# mcu.net
KiCad netlist of a schematic drawn in Altium Designer
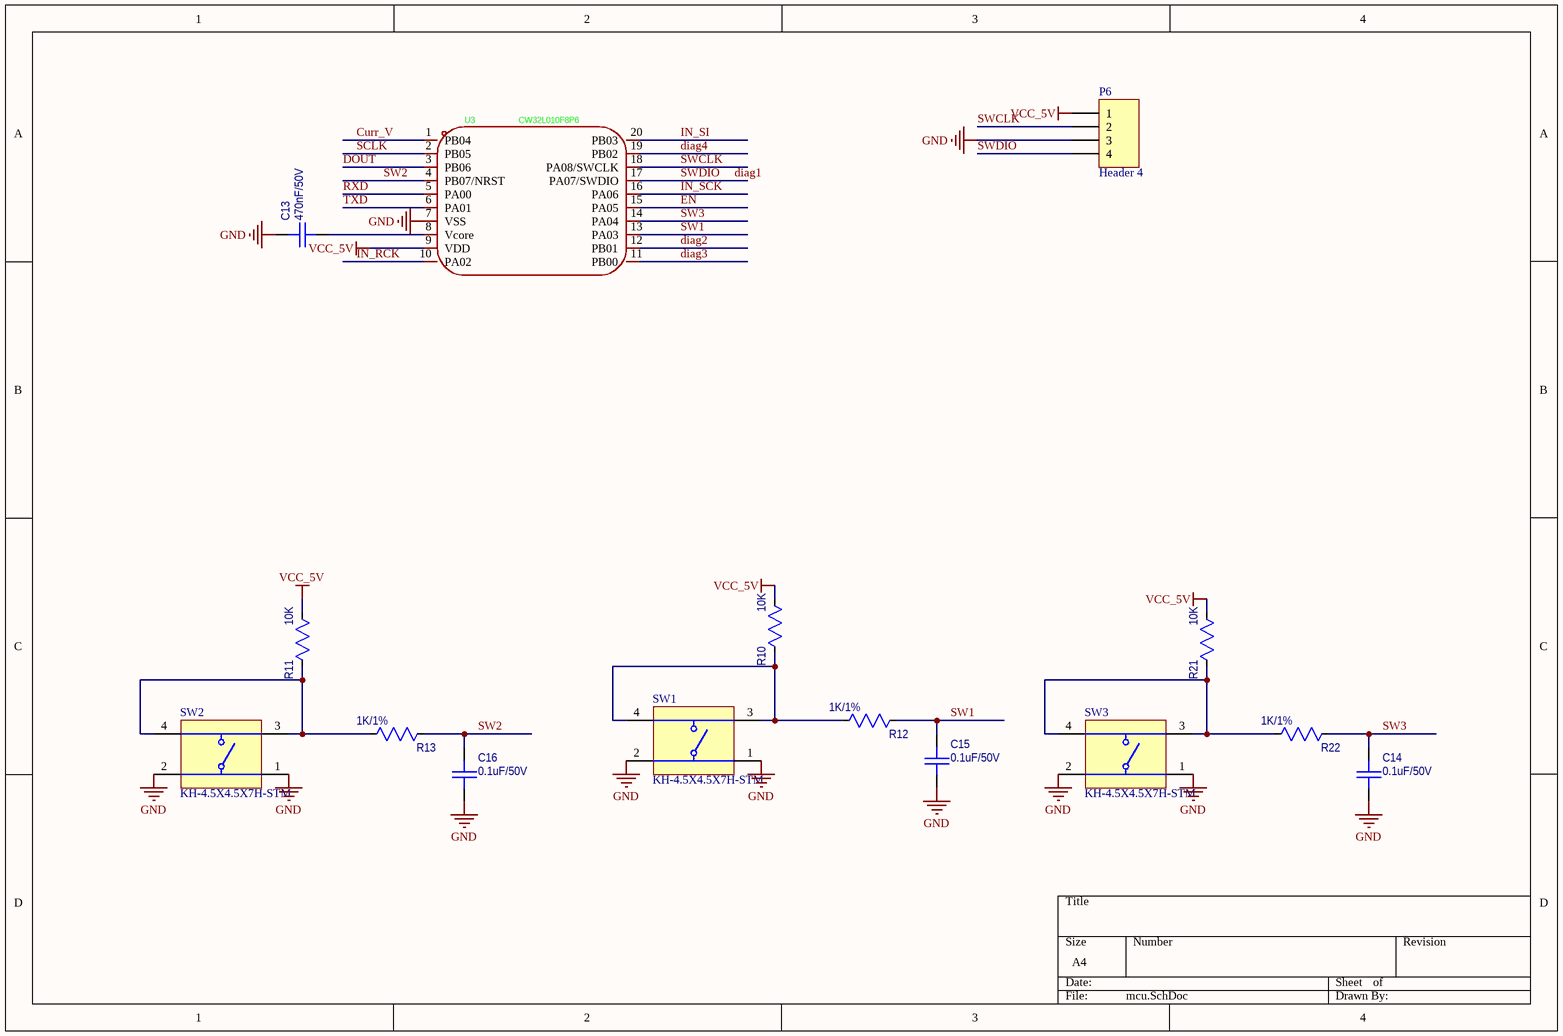
[diagram p0: mcu.SchDoc]

(export (version "E")
  (design (tool "Eeschema 10.0.6"))
  (components
    (comp (ref "C13")
      (value "470nF/50V")
      (footprint "CAPC1608X092N_0603")
      (description "Capacitor, MLCC")
      (fields (field (name "MANUFACTURER") "KEMET") (field (name "PARTNUMBER") "C0603C104M5RACTU"))
      (libsource (lib "Karl") (part "Capacitor_0603"))
    )
    (comp (ref "C14")
      (value "0.1uF/50V")
      (footprint "CAPC1608X092N_0603")
      (description "Capacitor, MLCC")
      (fields (field (name "MANUFACTURER") "KEMET") (field (name "PARTNUMBER") "C0603C104M5RACTU"))
      (libsource (lib "Karl") (part "Capacitor_0603"))
    )
    (comp (ref "C15")
      (value "0.1uF/50V")
      (footprint "CAPC1608X092N_0603")
      (description "Capacitor, MLCC")
      (fields (field (name "MANUFACTURER") "KEMET") (field (name "PARTNUMBER") "C0603C104M5RACTU"))
      (libsource (lib "Karl") (part "Capacitor_0603"))
    )
    (comp (ref "C16")
      (value "0.1uF/50V")
      (footprint "CAPC1608X092N_0603")
      (description "Capacitor, MLCC")
      (fields (field (name "MANUFACTURER") "KEMET") (field (name "PARTNUMBER") "C0603C104M5RACTU"))
      (libsource (lib "Karl") (part "Capacitor_0603"))
    )
    (comp (ref "P6")
      (value "Header 4")
      (footprint "1.27-4P")
      (fields (field (name "PUBLISHER") "Altium Limited"))
      (libsource (lib "Miscellaneous Connectors") (part "Header 4"))
    )
    (comp (ref "R10")
      (value "10K")
      (footprint "RESC1608X055N_0603")
      (description "Resistor, Standard")
      (fields (field (name "MANUFACTURER") "Yageo") (field (name "PARTNUMBER") "RC0603FR-1075KL"))
      (libsource (lib "Karl") (part "Resistor_0603"))
    )
    (comp (ref "R11")
      (value "10K")
      (footprint "RESC1608X055N_0603")
      (description "Resistor, Standard")
      (fields (field (name "MANUFACTURER") "Yageo") (field (name "PARTNUMBER") "RC0603FR-1075KL"))
      (libsource (lib "Karl") (part "Resistor_0603"))
    )
    (comp (ref "R12")
      (value "1K/1%")
      (footprint "RESC1608X055N_0603")
      (description "Resistor, Standard")
      (fields (field (name "MANUFACTURER") "Yageo") (field (name "PARTNUMBER") "RC0603FR-1075KL"))
      (libsource (lib "Karl") (part "Resistor_0603"))
    )
    (comp (ref "R13")
      (value "1K/1%")
      (footprint "RESC1608X055N_0603")
      (description "Resistor, Standard")
      (fields (field (name "MANUFACTURER") "Yageo") (field (name "PARTNUMBER") "RC0603FR-1075KL"))
      (libsource (lib "Karl") (part "Resistor_0603"))
    )
    (comp (ref "R21")
      (value "10K")
      (footprint "RESC1608X055N_0603")
      (description "Resistor, Standard")
      (fields (field (name "MANUFACTURER") "Yageo") (field (name "PARTNUMBER") "RC0603FR-1075KL"))
      (libsource (lib "Karl") (part "Resistor_0603"))
    )
    (comp (ref "R22")
      (value "1K/1%")
      (footprint "RESC1608X055N_0603")
      (description "Resistor, Standard")
      (fields (field (name "MANUFACTURER") "Yageo") (field (name "PARTNUMBER") "RC0603FR-1075KL"))
      (libsource (lib "Karl") (part "Resistor_0603"))
    )
    (comp (ref "SW1")
      (value "KH-4.5X4.5X7H-STM")
      (footprint "SW-SMD_4P-L4.5-W4.5-P3.00-LS6.8:SW-SMD_4P-L4.5-W4.5-P3.00-LS6.8")
      (description "Tactile Switch, 6 × 6 mm, Height 5.0mm, 4-Pin THD")
      (fields (field (name "PARTNUMBER") "J1L0503110"))
      (libsource (lib "Bogen") (part "J1L0503110"))
    )
    (comp (ref "SW2")
      (value "KH-4.5X4.5X7H-STM")
      (footprint "SW-SMD_4P-L4.5-W4.5-P3.00-LS6.8:SW-SMD_4P-L4.5-W4.5-P3.00-LS6.8")
      (description "Tactile Switch, 6 × 6 mm, Height 5.0mm, 4-Pin THD")
      (fields (field (name "PARTNUMBER") "J1L0503110"))
      (libsource (lib "Bogen") (part "J1L0503110"))
    )
    (comp (ref "SW3")
      (value "KH-4.5X4.5X7H-STM")
      (footprint "SW-SMD_4P-L4.5-W4.5-P3.00-LS6.8:SW-SMD_4P-L4.5-W4.5-P3.00-LS6.8")
      (description "Tactile Switch, 6 × 6 mm, Height 5.0mm, 4-Pin THD")
      (fields (field (name "PARTNUMBER") "J1L0503110"))
      (libsource (lib "Bogen") (part "J1L0503110"))
    )
    (comp (ref "U3")
      (value "CW32L010F8P6")
      (footprint "TSSOP-20_L6.5-W4.4-P0.65-LS6.4-BL:TSSOP-20_L6.5-W4.4-P0.65-LS6.4-BL")
      (fields (field (name "MANUFACTURER") "CW(芯源)"))
      (libsource (lib "altium-import") (part "root_0_CW32L010F8P6_"))
    )
  )
  (nets
    (net (code "1") (name "/Curr_V") (class "Default")
      (node (ref "U3") (pin "1") (pinfunction "PB04_1") (pintype "passive"))
    )
    (net (code "2") (name "/DOUT") (class "Default")
      (node (ref "U3") (pin "3") (pinfunction "PB06_3") (pintype "passive"))
    )
    (net (code "3") (name "/EN") (class "Default")
      (node (ref "U3") (pin "15") (pinfunction "PA05_15") (pintype "passive"))
    )
    (net (code "4") (name "/IN_RCK") (class "Default")
      (node (ref "U3") (pin "10") (pinfunction "PA02_10") (pintype "passive"))
    )
    (net (code "5") (name "/IN_SCK") (class "Default")
      (node (ref "U3") (pin "16") (pinfunction "PA06_16") (pintype "passive"))
    )
    (net (code "6") (name "/IN_SI") (class "Default")
      (node (ref "U3") (pin "20") (pinfunction "PB03_20") (pintype "passive"))
    )
    (net (code "7") (name "/RXD") (class "Default")
      (node (ref "U3") (pin "5") (pinfunction "PA00_5") (pintype "passive"))
    )
    (net (code "8") (name "/SCLK") (class "Default")
      (node (ref "U3") (pin "2") (pinfunction "PB05_2") (pintype "passive"))
    )
    (net (code "9") (name "/SW1") (class "Default")
      (node (ref "C15") (pin "1") (pinfunction "1_1") (pintype "passive"))
      (node (ref "R12") (pin "2") (pinfunction "2_2") (pintype "passive"))
      (node (ref "U3") (pin "13") (pinfunction "PA03_13") (pintype "passive"))
    )
    (net (code "10") (name "/SW2") (class "Default")
      (node (ref "C16") (pin "1") (pinfunction "1_1") (pintype "passive"))
      (node (ref "R13") (pin "2") (pinfunction "2_2") (pintype "passive"))
      (node (ref "U3") (pin "4") (pinfunction "PB07/NRST_4") (pintype "passive"))
    )
    (net (code "11") (name "/SW3") (class "Default")
      (node (ref "C14") (pin "1") (pinfunction "1_1") (pintype "passive"))
      (node (ref "R22") (pin "2") (pinfunction "2_2") (pintype "passive"))
      (node (ref "U3") (pin "14") (pinfunction "PA04_14") (pintype "passive"))
    )
    (net (code "12") (name "/SWCLK") (class "Default")
      (node (ref "P6") (pin "2") (pinfunction "2_2") (pintype "passive"))
      (node (ref "U3") (pin "18") (pinfunction "PA08/SWCLK_18") (pintype "passive"))
    )
    (net (code "13") (name "/SWDIO") (class "Default")
      (node (ref "P6") (pin "4") (pinfunction "4_4") (pintype "passive"))
      (node (ref "U3") (pin "17") (pinfunction "PA07/SWDIO_17") (pintype "passive"))
    )
    (net (code "14") (name "/TXD") (class "Default")
      (node (ref "U3") (pin "6") (pinfunction "PA01_6") (pintype "passive"))
    )
    (net (code "15") (name "/diag2") (class "Default")
      (node (ref "U3") (pin "12") (pinfunction "PB01_12") (pintype "passive"))
    )
    (net (code "16") (name "/diag3") (class "Default")
      (node (ref "U3") (pin "11") (pinfunction "PB00_11") (pintype "passive"))
    )
    (net (code "17") (name "/diag4") (class "Default")
      (node (ref "U3") (pin "19") (pinfunction "PB02_19") (pintype "passive"))
    )
    (net (code "18") (name "GND") (class "Default")
      (node (ref "C13") (pin "1") (pinfunction "1_1") (pintype "passive"))
      (node (ref "C14") (pin "2") (pinfunction "2_2") (pintype "passive"))
      (node (ref "C15") (pin "2") (pinfunction "2_2") (pintype "passive"))
      (node (ref "C16") (pin "2") (pinfunction "2_2") (pintype "passive"))
      (node (ref "P6") (pin "3") (pinfunction "3_3") (pintype "passive"))
      (node (ref "SW1") (pin "1") (pinfunction "1_1") (pintype "passive"))
      (node (ref "SW1") (pin "2") (pinfunction "2_2") (pintype "passive"))
      (node (ref "SW2") (pin "1") (pinfunction "1_1") (pintype "passive"))
      (node (ref "SW2") (pin "2") (pinfunction "2_2") (pintype "passive"))
      (node (ref "SW3") (pin "1") (pinfunction "1_1") (pintype "passive"))
      (node (ref "SW3") (pin "2") (pinfunction "2_2") (pintype "passive"))
      (node (ref "U3") (pin "7") (pinfunction "VSS_7") (pintype "passive"))
    )
    (net (code "19") (name "Net-(R10-Pad2)") (class "Default")
      (node (ref "R10") (pin "2") (pinfunction "2_2") (pintype "passive"))
      (node (ref "R12") (pin "1") (pinfunction "1_1") (pintype "passive"))
      (node (ref "SW1") (pin "3") (pinfunction "3_3") (pintype "passive"))
      (node (ref "SW1") (pin "4") (pinfunction "4_4") (pintype "passive"))
    )
    (net (code "20") (name "Net-(R11-Pad2)") (class "Default")
      (node (ref "R11") (pin "2") (pinfunction "2_2") (pintype "passive"))
      (node (ref "R13") (pin "1") (pinfunction "1_1") (pintype "passive"))
      (node (ref "SW2") (pin "3") (pinfunction "3_3") (pintype "passive"))
      (node (ref "SW2") (pin "4") (pinfunction "4_4") (pintype "passive"))
    )
    (net (code "21") (name "Net-(R21-Pad2)") (class "Default")
      (node (ref "R21") (pin "2") (pinfunction "2_2") (pintype "passive"))
      (node (ref "R22") (pin "1") (pinfunction "1_1") (pintype "passive"))
      (node (ref "SW3") (pin "3") (pinfunction "3_3") (pintype "passive"))
      (node (ref "SW3") (pin "4") (pinfunction "4_4") (pintype "passive"))
    )
    (net (code "22") (name "Net-(U3-Vcore)") (class "Default")
      (node (ref "C13") (pin "2") (pinfunction "2_2") (pintype "passive"))
      (node (ref "U3") (pin "8") (pinfunction "Vcore_8") (pintype "passive"))
    )
    (net (code "23") (name "VCC_5V") (class "Default")
      (node (ref "P6") (pin "1") (pinfunction "1_1") (pintype "passive"))
      (node (ref "R10") (pin "1") (pinfunction "1_1") (pintype "passive"))
      (node (ref "R11") (pin "1") (pinfunction "1_1") (pintype "passive"))
      (node (ref "R21") (pin "1") (pinfunction "1_1") (pintype "passive"))
      (node (ref "U3") (pin "9") (pinfunction "VDD_9") (pintype "passive"))
    )
  )
)
